# untitled.net
KiCad netlist of a schematic drawn in EAGLE
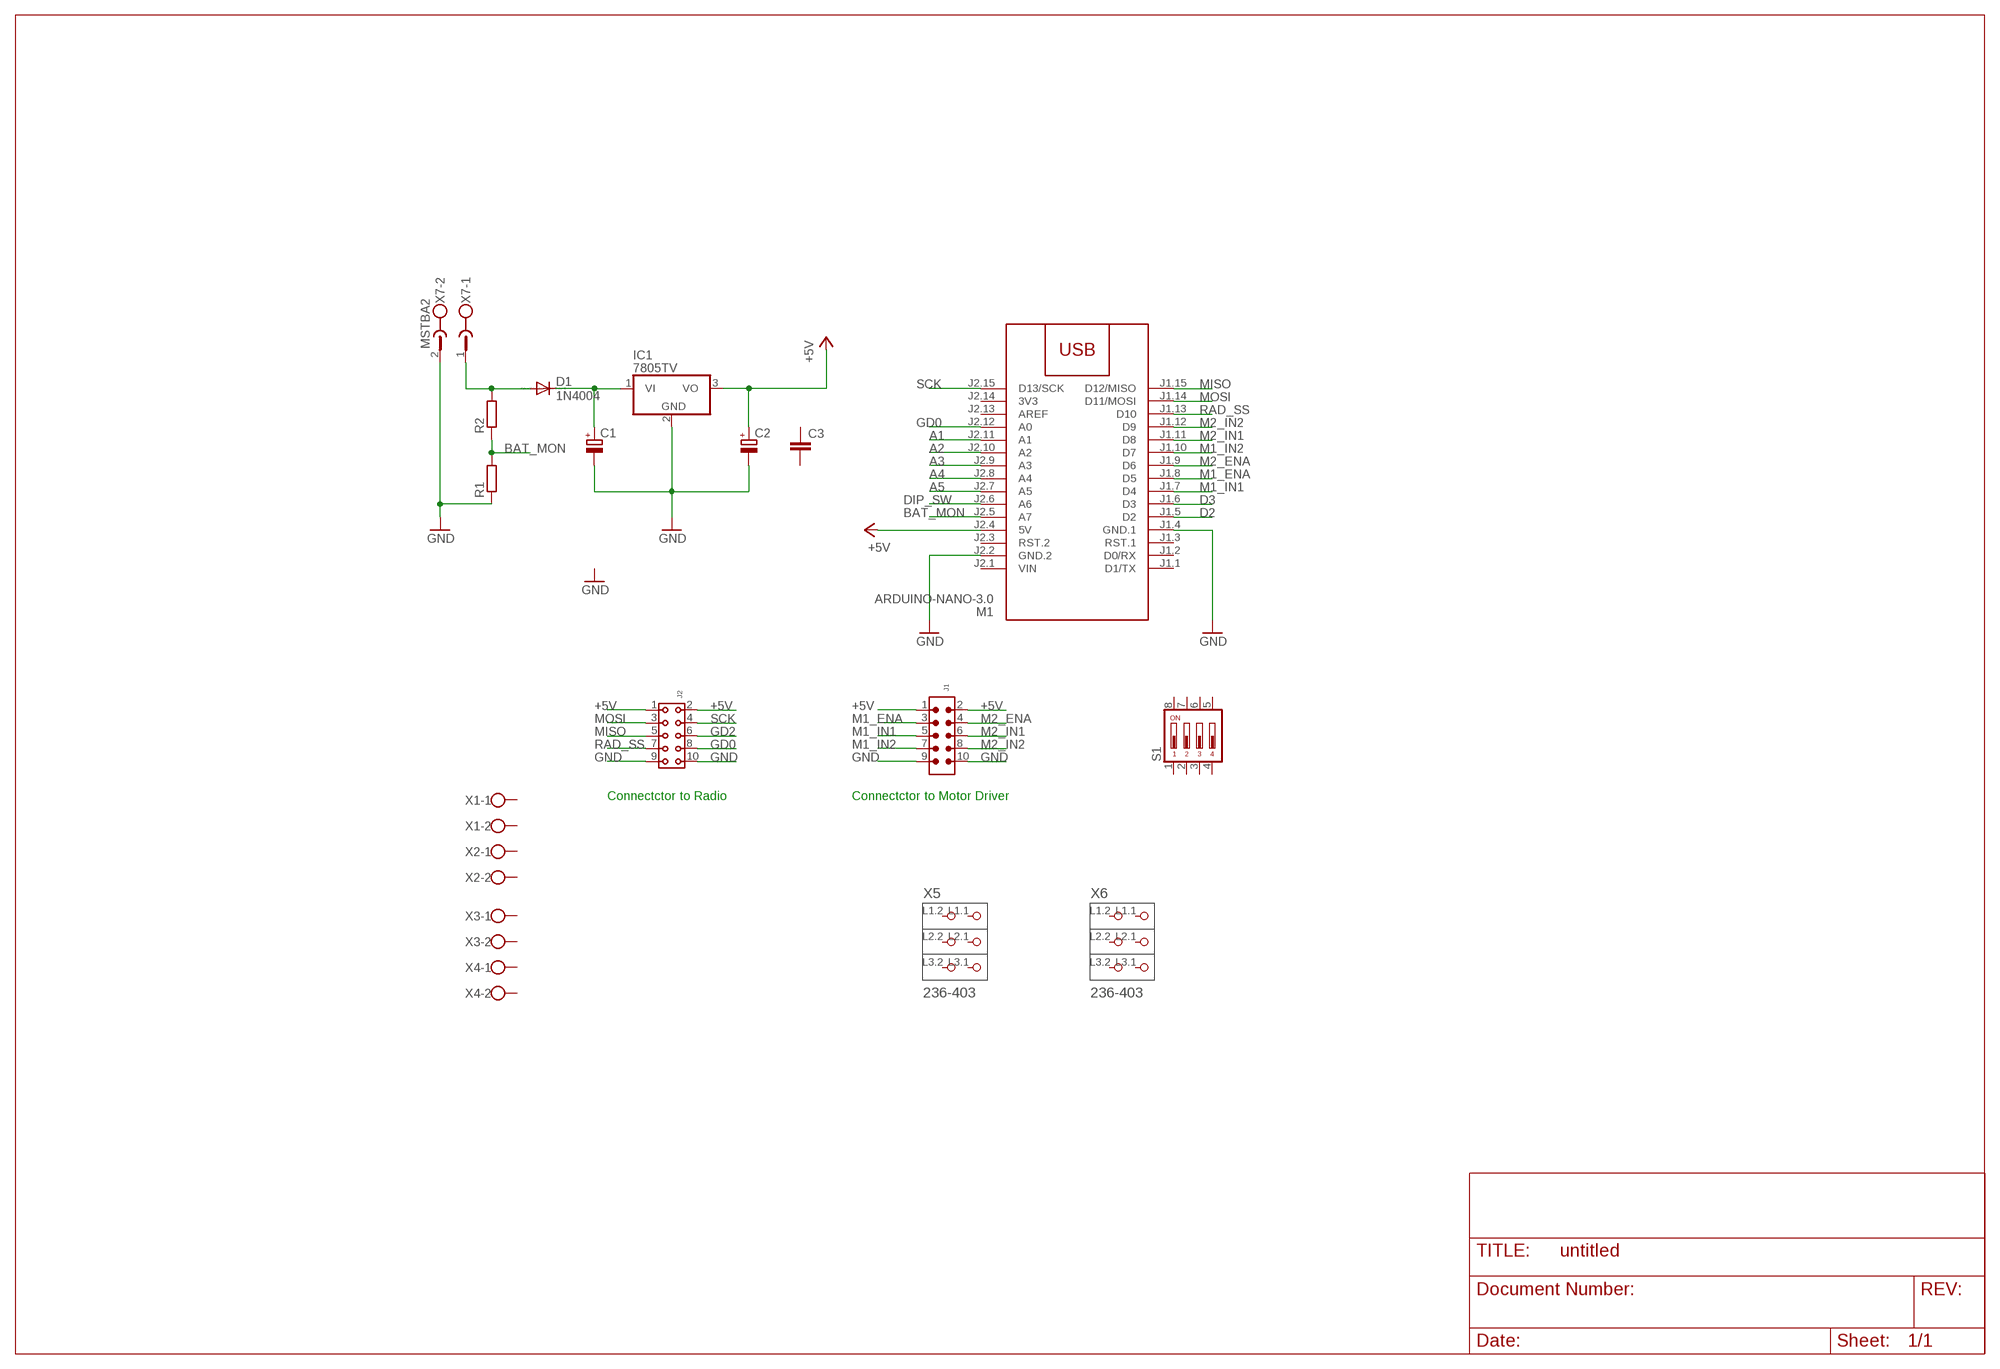
[diagram p0: schematic, sheet 1]

(export (version "E")
  (design (tool "Eeschema 10.0.6"))
  (components
    (comp (ref "C1")
      (value "CPOL-EUE10-20")
      (footprint "eagle-import:EB20D")
      (libsource (lib "eagle-import") (part "CPOL-EUE10-20"))
    )
    (comp (ref "C2")
      (value "CPOL-EUE10-20")
      (footprint "eagle-import:EB20D")
      (libsource (lib "eagle-import") (part "CPOL-EUE10-20"))
    )
    (comp (ref "C3")
      (value "C-EU050-030X075")
      (footprint "eagle-import:C050-030X075")
      (libsource (lib "eagle-import") (part "C-EU050-030X075"))
    )
    (comp (ref "D1")
      (value "1N4004")
      (footprint "eagle-import:DO41-10")
      (libsource (lib "eagle-import") (part "1N4004"))
    )
    (comp (ref "IC1")
      (value "7805TV")
      (footprint "eagle-import:TO220V")
      (libsource (lib "eagle-import") (part "78TV05"))
    )
    (comp (ref "J1")
      (value "6120XX21621_61201021621")
      (footprint "eagle-import:61201021621")
      (libsource (lib "eagle-import") (part "6120XX21621_61201021621"))
    )
    (comp (ref "J2")
      (value "6130XX21821_61301021821")
      (footprint "eagle-import:61301021821")
      (libsource (lib "eagle-import") (part "6130XX21821_61301021821"))
    )
    (comp (ref "M1")
      (value "ARDUINO-NANO-3.0")
      (footprint "eagle-import:ARDUINO-NANO-3.0")
      (libsource (lib "eagle-import") (part "ARDUINO-NANO-3.0"))
    )
    (comp (ref "R1")
      (value "R-EU_0207/7")
      (footprint "eagle-import:0207_7")
      (libsource (lib "eagle-import") (part "R-EU_0207/7"))
    )
    (comp (ref "R2")
      (value "R-EU_0207/7")
      (footprint "eagle-import:0207_7")
      (libsource (lib "eagle-import") (part "R-EU_0207/7"))
    )
    (comp (ref "S1")
      (value "DIP04YL")
      (footprint "eagle-import:DIP04YL")
      (libsource (lib "eagle-import") (part "DIP04YL"))
    )
    (comp (ref "X1")
      (value "W237-102")
      (footprint "eagle-import:W237-102")
      (fields (field (name "MPN") "237-102"))
      (libsource (lib "eagle-import") (part "W237-102"))
    )
    (comp (ref "X2")
      (value "W237-102")
      (footprint "eagle-import:W237-102")
      (fields (field (name "MPN") "237-102"))
      (libsource (lib "eagle-import") (part "W237-102"))
    )
    (comp (ref "X3")
      (value "W237-102")
      (footprint "eagle-import:W237-102")
      (fields (field (name "MPN") "237-102"))
      (libsource (lib "eagle-import") (part "W237-102"))
    )
    (comp (ref "X4")
      (value "W237-102")
      (footprint "eagle-import:W237-102")
      (fields (field (name "MPN") "237-102"))
      (libsource (lib "eagle-import") (part "W237-102"))
    )
    (comp (ref "X5")
      (value "236-403")
      (footprint "eagle-import:P-236-403")
      (libsource (lib "eagle-import") (part "236-403"))
    )
    (comp (ref "X6")
      (value "236-403")
      (footprint "eagle-import:P-236-403")
      (libsource (lib "eagle-import") (part "236-403"))
    )
    (comp (ref "X7")
      (value "MSTBA2")
      (footprint "eagle-import:MSTBA2")
      (fields (field (name "MF") "FARNELL") (field (name "MPN") "1757242"))
      (libsource (lib "eagle-import") (part "MSTBA2"))
    )
  )
  (nets
    (net (code "1") (name "+5V") (class "Default")
      (node (ref "C2") (pin "+") (pinfunction "+_+") (pintype "passive"))
      (node (ref "IC1") (pin "3") (pinfunction "VO_3") (pintype "passive"))
      (node (ref "J1") (pin "1") (pinfunction "1_1") (pintype "passive"))
      (node (ref "J1") (pin "2") (pinfunction "2_2") (pintype "passive"))
      (node (ref "J2") (pin "1") (pinfunction "1_1") (pintype "passive"))
      (node (ref "J2") (pin "2") (pinfunction "2_2") (pintype "passive"))
      (node (ref "M1") (pin "J2.4") (pinfunction "5V_J2.4") (pintype "power_in"))
    )
    (net (code "2") (name "/3V3") (class "Default")
      (node (ref "M1") (pin "J2.14") (pinfunction "3V3_J2.14") (pintype "power_in"))
    )
    (net (code "3") (name "/A1") (class "Default")
      (node (ref "M1") (pin "J2.11") (pinfunction "A1_J2.11") (pintype "bidirectional"))
    )
    (net (code "4") (name "/A2") (class "Default")
      (node (ref "M1") (pin "J2.10") (pinfunction "A2_J2.10") (pintype "bidirectional"))
    )
    (net (code "5") (name "/A3") (class "Default")
      (node (ref "M1") (pin "J2.9") (pinfunction "A3_J2.9") (pintype "bidirectional"))
    )
    (net (code "6") (name "/A4") (class "Default")
      (node (ref "M1") (pin "J2.8") (pinfunction "A4_J2.8") (pintype "bidirectional"))
    )
    (net (code "7") (name "/A5") (class "Default")
      (node (ref "M1") (pin "J2.7") (pinfunction "A5_J2.7") (pintype "bidirectional"))
    )
    (net (code "8") (name "/BAT_MON") (class "Default")
      (node (ref "M1") (pin "J2.5") (pinfunction "A7_J2.5") (pintype "bidirectional"))
      (node (ref "R1") (pin "2") (pinfunction "2_2") (pintype "passive"))
      (node (ref "R2") (pin "1") (pinfunction "1_1") (pintype "passive"))
    )
    (net (code "9") (name "/D2") (class "Default")
      (node (ref "M1") (pin "J1.5") (pinfunction "D2_J1.5") (pintype "bidirectional"))
    )
    (net (code "10") (name "/D3") (class "Default")
      (node (ref "M1") (pin "J1.6") (pinfunction "D3_J1.6") (pintype "bidirectional"))
    )
    (net (code "11") (name "/DIP_SW") (class "Default")
      (node (ref "M1") (pin "J2.6") (pinfunction "A6_J2.6") (pintype "bidirectional"))
    )
    (net (code "12") (name "/GD0") (class "Default")
      (node (ref "J2") (pin "8") (pinfunction "8_8") (pintype "passive"))
      (node (ref "M1") (pin "J2.12") (pinfunction "A0_J2.12") (pintype "bidirectional"))
    )
    (net (code "13") (name "/GD2") (class "Default")
      (node (ref "J2") (pin "6") (pinfunction "6_6") (pintype "passive"))
    )
    (net (code "14") (name "/M1_ENA") (class "Default")
      (node (ref "J1") (pin "3") (pinfunction "3_3") (pintype "passive"))
      (node (ref "M1") (pin "J1.8") (pinfunction "D5_J1.8") (pintype "bidirectional"))
    )
    (net (code "15") (name "/M1_IN1") (class "Default")
      (node (ref "J1") (pin "5") (pinfunction "5_5") (pintype "passive"))
      (node (ref "M1") (pin "J1.7") (pinfunction "D4_J1.7") (pintype "bidirectional"))
    )
    (net (code "16") (name "/M1_IN2") (class "Default")
      (node (ref "J1") (pin "7") (pinfunction "7_7") (pintype "passive"))
      (node (ref "M1") (pin "J1.10") (pinfunction "D7_J1.10") (pintype "bidirectional"))
    )
    (net (code "17") (name "/M2_ENA") (class "Default")
      (node (ref "J1") (pin "4") (pinfunction "4_4") (pintype "passive"))
      (node (ref "M1") (pin "J1.9") (pinfunction "D6_J1.9") (pintype "bidirectional"))
    )
    (net (code "18") (name "/M2_IN1") (class "Default")
      (node (ref "J1") (pin "6") (pinfunction "6_6") (pintype "passive"))
      (node (ref "M1") (pin "J1.11") (pinfunction "D8_J1.11") (pintype "bidirectional"))
    )
    (net (code "19") (name "/M2_IN2") (class "Default")
      (node (ref "J1") (pin "8") (pinfunction "8_8") (pintype "passive"))
      (node (ref "M1") (pin "J1.12") (pinfunction "D9_J1.12") (pintype "bidirectional"))
    )
    (net (code "20") (name "/MISO") (class "Default")
      (node (ref "J2") (pin "5") (pinfunction "5_5") (pintype "passive"))
      (node (ref "M1") (pin "J1.15") (pinfunction "D12/MISO_J1.15") (pintype "bidirectional"))
    )
    (net (code "21") (name "/MOSI") (class "Default")
      (node (ref "J2") (pin "3") (pinfunction "3_3") (pintype "passive"))
      (node (ref "M1") (pin "J1.14") (pinfunction "D11/MOSI_J1.14") (pintype "bidirectional"))
    )
    (net (code "22") (name "/RAD_SS") (class "Default")
      (node (ref "J2") (pin "7") (pinfunction "7_7") (pintype "passive"))
      (node (ref "M1") (pin "J1.13") (pinfunction "D10_J1.13") (pintype "bidirectional"))
    )
    (net (code "23") (name "/SCK") (class "Default")
      (node (ref "J2") (pin "4") (pinfunction "4_4") (pintype "passive"))
      (node (ref "M1") (pin "J2.15") (pinfunction "D13/SCK_J2.15") (pintype "bidirectional"))
    )
    (net (code "24") (name "/VIN") (class "Default")
      (node (ref "M1") (pin "J2.1") (pinfunction "VIN_J2.1") (pintype "power_in"))
    )
    (net (code "25") (name "GND") (class "Default")
      (node (ref "C1") (pin "-") (pinfunction "-_-") (pintype "passive"))
      (node (ref "C2") (pin "-") (pinfunction "-_-") (pintype "passive"))
      (node (ref "IC1") (pin "2") (pinfunction "GND_2") (pintype "passive"))
      (node (ref "J1") (pin "10") (pinfunction "10_10") (pintype "passive"))
      (node (ref "J1") (pin "9") (pinfunction "9_9") (pintype "passive"))
      (node (ref "J2") (pin "10") (pinfunction "10_10") (pintype "passive"))
      (node (ref "J2") (pin "9") (pinfunction "9_9") (pintype "passive"))
      (node (ref "M1") (pin "J1.4") (pinfunction "GND.1_J1.4") (pintype "power_in"))
      (node (ref "M1") (pin "J2.2") (pinfunction "GND.2_J2.2") (pintype "power_in"))
      (node (ref "R1") (pin "1") (pinfunction "1_1") (pintype "passive"))
      (node (ref "X7") (pin "2") (pinfunction "1_2") (pintype "passive"))
    )
    (net (code "26") (name "Net-(D1-PadA)") (class "Default")
      (node (ref "D1") (pin "A") (pinfunction "A_A") (pintype "passive"))
      (node (ref "R2") (pin "2") (pinfunction "2_2") (pintype "passive"))
      (node (ref "X7") (pin "1") (pinfunction "1_1") (pintype "passive"))
    )
    (net (code "27") (name "Net-(IC1-VI)") (class "Default")
      (node (ref "C1") (pin "+") (pinfunction "+_+") (pintype "passive"))
      (node (ref "D1") (pin "C") (pinfunction "C_C") (pintype "passive"))
      (node (ref "IC1") (pin "1") (pinfunction "VI_1") (pintype "input"))
    )
    (net (code "28") (name "unconnected-(C3-Pad1)") (class "Default")
      (node (ref "C3") (pin "1") (pinfunction "1_1") (pintype "passive"))
    )
    (net (code "29") (name "unconnected-(C3-Pad2)") (class "Default")
      (node (ref "C3") (pin "2") (pinfunction "2_2") (pintype "passive"))
    )
    (net (code "30") (name "unconnected-(M1-AREF-PadJ2.13)") (class "Default")
      (node (ref "M1") (pin "J2.13") (pinfunction "AREF_J2.13") (pintype "bidirectional"))
    )
    (net (code "31") (name "unconnected-(M1-D0{slash}RX-PadJ1.2)") (class "Default")
      (node (ref "M1") (pin "J1.2") (pinfunction "D0/RX_J1.2") (pintype "bidirectional"))
    )
    (net (code "32") (name "unconnected-(M1-D1{slash}TX-PadJ1.1)") (class "Default")
      (node (ref "M1") (pin "J1.1") (pinfunction "D1/TX_J1.1") (pintype "bidirectional"))
    )
    (net (code "33") (name "unconnected-(M1-RST.1-PadJ1.3)") (class "Default")
      (node (ref "M1") (pin "J1.3") (pinfunction "RST.1_J1.3") (pintype "bidirectional"))
    )
    (net (code "34") (name "unconnected-(M1-RST.2-PadJ2.3)") (class "Default")
      (node (ref "M1") (pin "J2.3") (pinfunction "RST.2_J2.3") (pintype "bidirectional"))
    )
    (net (code "35") (name "unconnected-(S1-Pad1)") (class "Default")
      (node (ref "S1") (pin "1") (pinfunction "1_1") (pintype "passive"))
    )
    (net (code "36") (name "unconnected-(S1-Pad2)") (class "Default")
      (node (ref "S1") (pin "2") (pinfunction "2_2") (pintype "passive"))
    )
    (net (code "37") (name "unconnected-(S1-Pad3)") (class "Default")
      (node (ref "S1") (pin "3") (pinfunction "3_3") (pintype "passive"))
    )
    (net (code "38") (name "unconnected-(S1-Pad4)") (class "Default")
      (node (ref "S1") (pin "4") (pinfunction "4_4") (pintype "passive"))
    )
    (net (code "39") (name "unconnected-(S1-Pad5)") (class "Default")
      (node (ref "S1") (pin "5") (pinfunction "5_5") (pintype "passive"))
    )
    (net (code "40") (name "unconnected-(S1-Pad6)") (class "Default")
      (node (ref "S1") (pin "6") (pinfunction "6_6") (pintype "passive"))
    )
    (net (code "41") (name "unconnected-(S1-Pad7)") (class "Default")
      (node (ref "S1") (pin "7") (pinfunction "7_7") (pintype "passive"))
    )
    (net (code "42") (name "unconnected-(S1-Pad8)") (class "Default")
      (node (ref "S1") (pin "8") (pinfunction "8_8") (pintype "passive"))
    )
    (net (code "43") (name "unconnected-(X1A-KL-Pad1)") (class "Default")
      (node (ref "X1") (pin "1") (pinfunction "KL_1") (pintype "passive"))
    )
    (net (code "44") (name "unconnected-(X1B-KL-Pad2)") (class "Default")
      (node (ref "X1") (pin "2") (pinfunction "KL_2") (pintype "passive"))
    )
    (net (code "45") (name "unconnected-(X2A-KL-Pad1)") (class "Default")
      (node (ref "X2") (pin "1") (pinfunction "KL_1") (pintype "passive"))
    )
    (net (code "46") (name "unconnected-(X2B-KL-Pad2)") (class "Default")
      (node (ref "X2") (pin "2") (pinfunction "KL_2") (pintype "passive"))
    )
    (net (code "47") (name "unconnected-(X3A-KL-Pad1)") (class "Default")
      (node (ref "X3") (pin "1") (pinfunction "KL_1") (pintype "passive"))
    )
    (net (code "48") (name "unconnected-(X3B-KL-Pad2)") (class "Default")
      (node (ref "X3") (pin "2") (pinfunction "KL_2") (pintype "passive"))
    )
    (net (code "49") (name "unconnected-(X4A-KL-Pad1)") (class "Default")
      (node (ref "X4") (pin "1") (pinfunction "KL_1") (pintype "passive"))
    )
    (net (code "50") (name "unconnected-(X4B-KL-Pad2)") (class "Default")
      (node (ref "X4") (pin "2") (pinfunction "KL_2") (pintype "passive"))
    )
    (net (code "51") (name "unconnected-(X5-P1.1-PadL1.1)") (class "Default")
      (node (ref "X5") (pin "L1.1") (pinfunction "P1.1_L1.1") (pintype "bidirectional"))
    )
    (net (code "52") (name "unconnected-(X5-P1.2-PadL1.2)") (class "Default")
      (node (ref "X5") (pin "L1.2") (pinfunction "P1.2_L1.2") (pintype "bidirectional"))
    )
    (net (code "53") (name "unconnected-(X5-P2.1-PadL2.1)") (class "Default")
      (node (ref "X5") (pin "L2.1") (pinfunction "P2.1_L2.1") (pintype "bidirectional"))
    )
    (net (code "54") (name "unconnected-(X5-P2.2-PadL2.2)") (class "Default")
      (node (ref "X5") (pin "L2.2") (pinfunction "P2.2_L2.2") (pintype "bidirectional"))
    )
    (net (code "55") (name "unconnected-(X5-P3.1-PadL3.1)") (class "Default")
      (node (ref "X5") (pin "L3.1") (pinfunction "P3.1_L3.1") (pintype "bidirectional"))
    )
    (net (code "56") (name "unconnected-(X5-P3.2-PadL3.2)") (class "Default")
      (node (ref "X5") (pin "L3.2") (pinfunction "P3.2_L3.2") (pintype "bidirectional"))
    )
    (net (code "57") (name "unconnected-(X6-P1.1-PadL1.1)") (class "Default")
      (node (ref "X6") (pin "L1.1") (pinfunction "P1.1_L1.1") (pintype "bidirectional"))
    )
    (net (code "58") (name "unconnected-(X6-P1.2-PadL1.2)") (class "Default")
      (node (ref "X6") (pin "L1.2") (pinfunction "P1.2_L1.2") (pintype "bidirectional"))
    )
    (net (code "59") (name "unconnected-(X6-P2.1-PadL2.1)") (class "Default")
      (node (ref "X6") (pin "L2.1") (pinfunction "P2.1_L2.1") (pintype "bidirectional"))
    )
    (net (code "60") (name "unconnected-(X6-P2.2-PadL2.2)") (class "Default")
      (node (ref "X6") (pin "L2.2") (pinfunction "P2.2_L2.2") (pintype "bidirectional"))
    )
    (net (code "61") (name "unconnected-(X6-P3.1-PadL3.1)") (class "Default")
      (node (ref "X6") (pin "L3.1") (pinfunction "P3.1_L3.1") (pintype "bidirectional"))
    )
    (net (code "62") (name "unconnected-(X6-P3.2-PadL3.2)") (class "Default")
      (node (ref "X6") (pin "L3.2") (pinfunction "P3.2_L3.2") (pintype "bidirectional"))
    )
  )
)
